# Schematic.net
KiCad netlist of a schematic drawn in Altium Designer
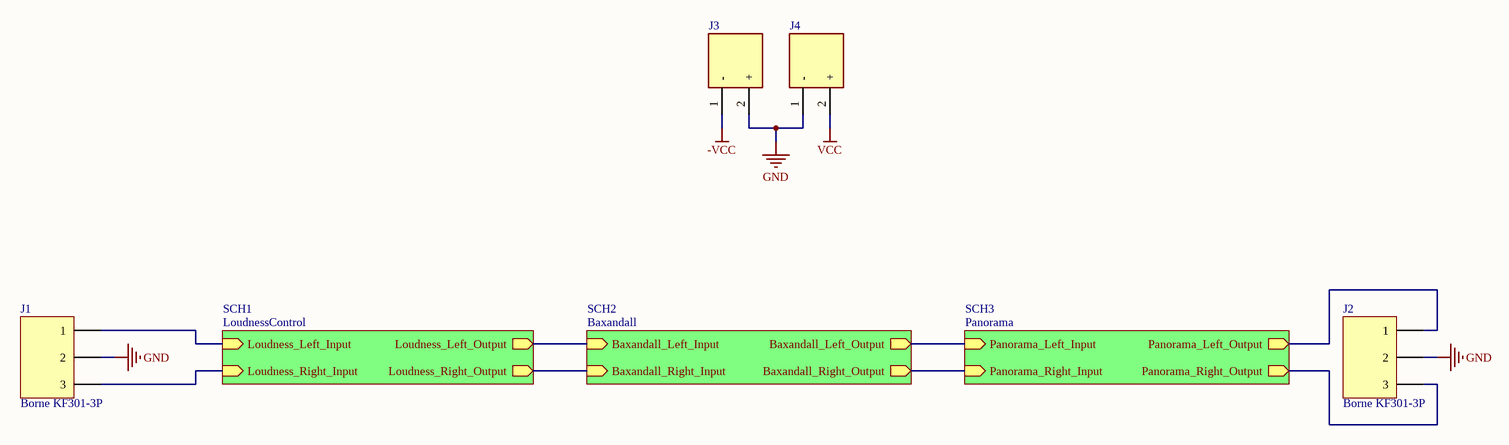
[diagram p0: Schematic.SchDoc]

(export (version "E")
  (design (tool "Eeschema 10.0.6"))
  (components
    (comp (ref "J1")
      (value "Borne KF301-3P")
      (footprint "Borne KF301-3P")
      (libsource (lib "AltiumLibrary-Mugetsu") (part "Borne KF301-3P"))
    )
    (comp (ref "J2")
      (value "Borne KF301-3P")
      (footprint "Borne KF301-3P")
      (libsource (lib "AltiumLibrary-Mugetsu") (part "Borne KF301-3P"))
    )
    (comp (ref "J3")
      (value "Borne KF301-2P")
      (footprint "Borne KF301-2P")
      (description "2 Pin Terminal Block 5mm Pitch")
      (fields (field (name "MP") "KF301-2P"))
      (libsource (lib "AltiumLibrary-Mugetsu") (part "Borne KF301-2P"))
    )
    (comp (ref "J4")
      (value "Borne KF301-2P")
      (footprint "Borne KF301-2P")
      (description "2 Pin Terminal Block 5mm Pitch")
      (fields (field (name "MP") "KF301-2P"))
      (libsource (lib "AltiumLibrary-Mugetsu") (part "Borne KF301-2P"))
    )
  )
  (nets
    (net (code "1") (name "-VCC") (class "Default")
      (node (ref "J3") (pin "1") (pinfunction "-_1") (pintype "passive"))
    )
    (net (code "4") (name "/Loudness_Left_Input") (class "Default")
      (node (ref "J1") (pin "1") (pinfunction "1_1") (pintype "passive"))
    )
    (net (code "6") (name "/Loudness_Right_Input") (class "Default")
      (node (ref "J1") (pin "3") (pinfunction "3_3") (pintype "passive"))
    )
    (net (code "8") (name "/Panorama_Left_Output") (class "Default")
      (node (ref "J2") (pin "1") (pinfunction "1_1") (pintype "passive"))
    )
    (net (code "9") (name "/Panorama_Right_Output") (class "Default")
      (node (ref "J2") (pin "3") (pinfunction "3_3") (pintype "passive"))
    )
    (net (code "10") (name "GND") (class "Default")
      (node (ref "J1") (pin "2") (pinfunction "2_2") (pintype "passive"))
      (node (ref "J2") (pin "2") (pinfunction "2_2") (pintype "passive"))
      (node (ref "J3") (pin "2") (pinfunction "+_2") (pintype "passive"))
      (node (ref "J4") (pin "1") (pinfunction "-_1") (pintype "passive"))
    )
    (net (code "11") (name "VCC") (class "Default")
      (node (ref "J4") (pin "2") (pinfunction "+_2") (pintype "passive"))
    )
  )
)
